# powertrain.net
KiCad netlist of a schematic drawn in Altium Designer
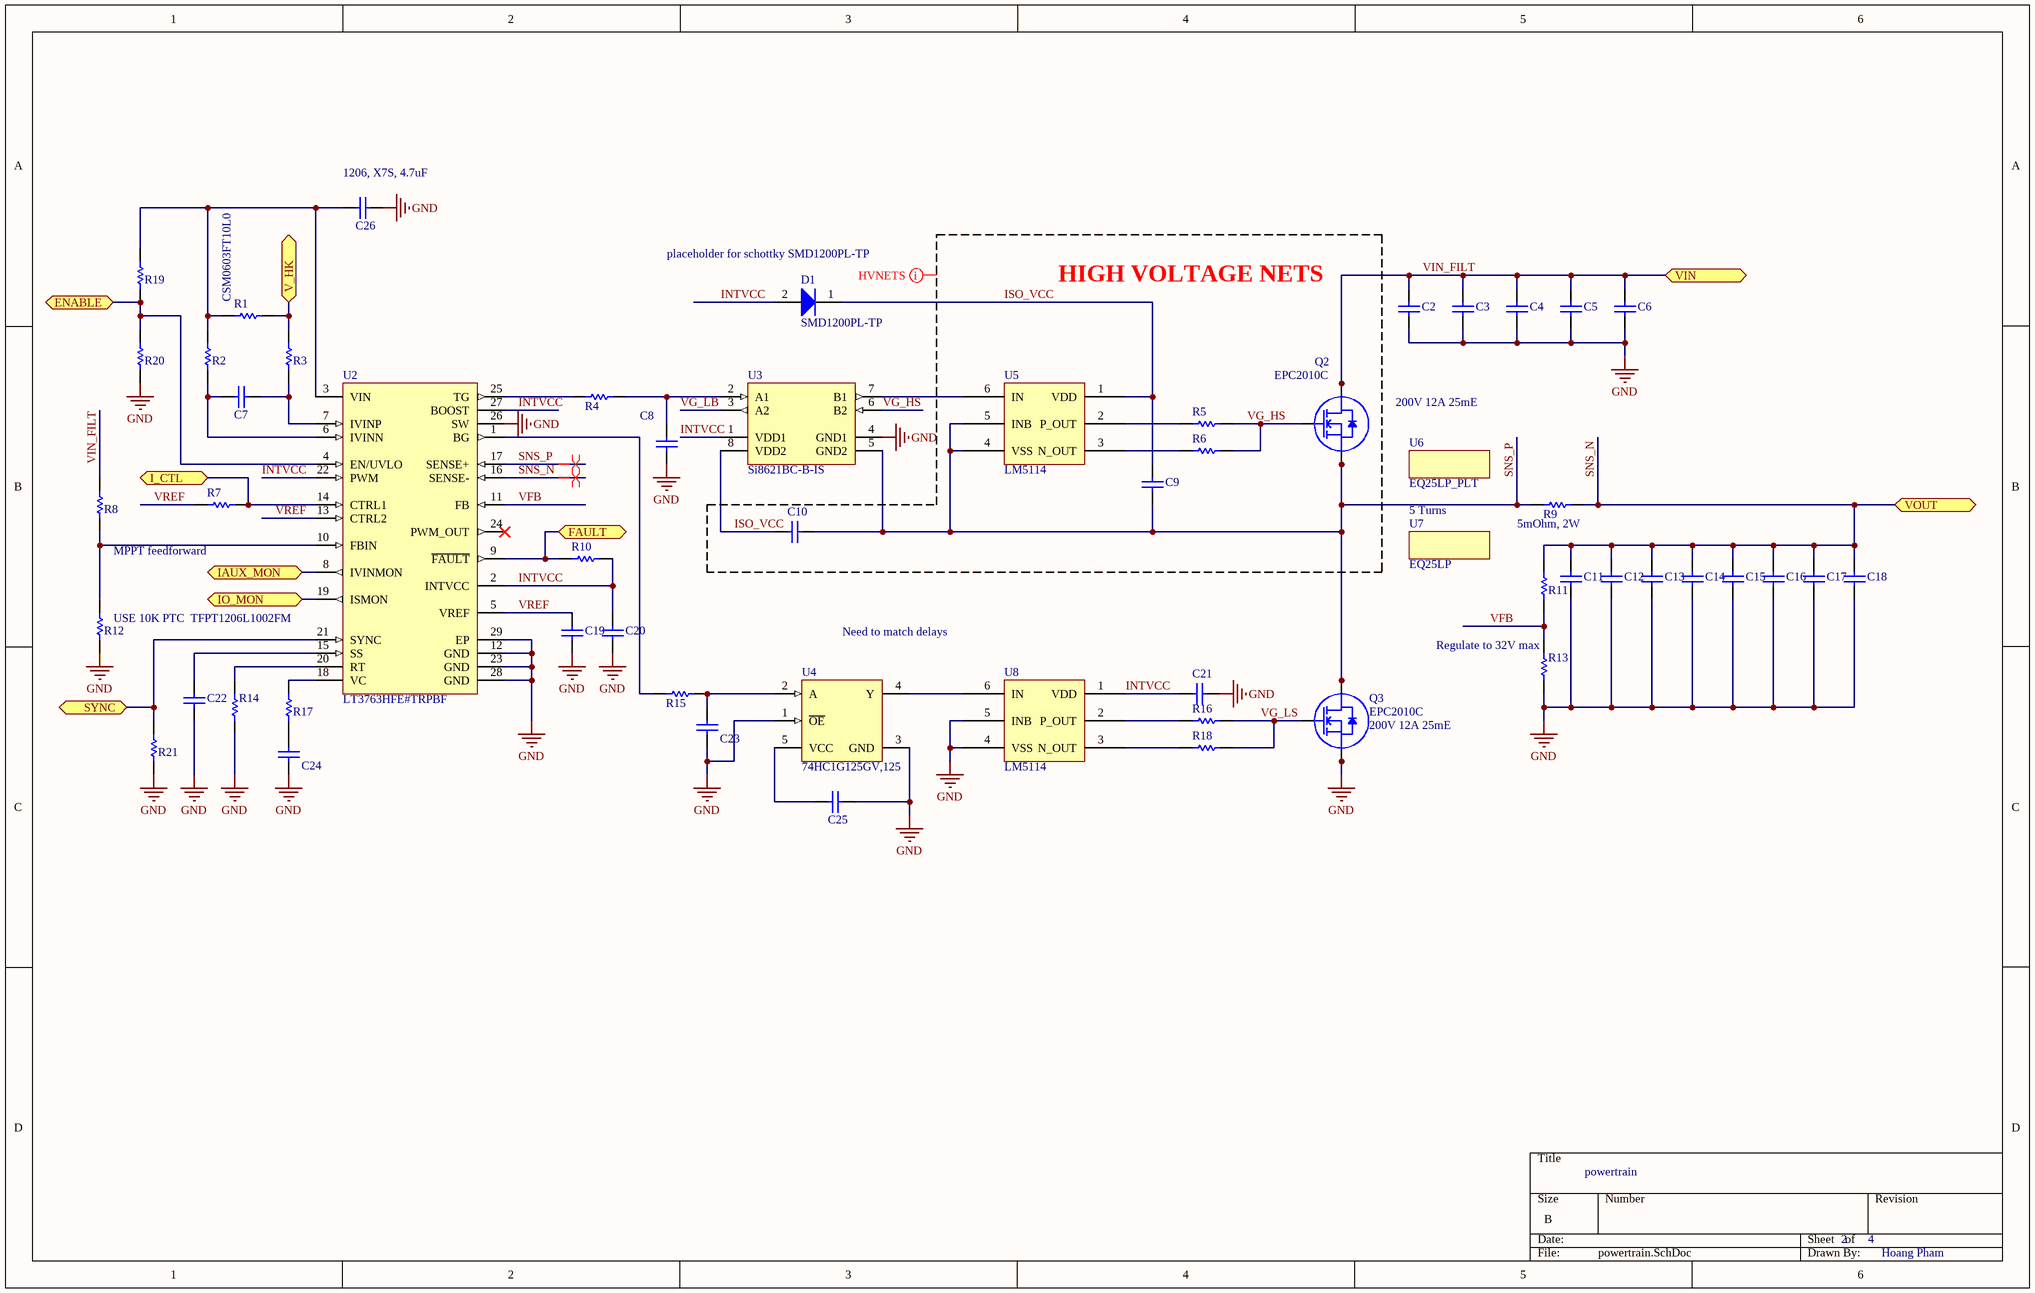
[diagram p0: powertrain.SchDoc]

(export (version "E")
  (design (tool "Eeschema 10.0.6"))
  (components
    (comp (ref "C2")
      (value "CAP 10nF 200V 0603(1608)")
      (footprint "CAPC0603(1608)100_L")
      (description "CAP 10nF 200V ±10% 0603 (1608 Metric) Thickness 1mm SMD")
      (fields (field (name "TOLERANCE") "Â±10%"))
      (libsource (lib "Altium Content Vault") (part "CAP"))
    )
    (comp (ref "C3")
      (value "CAP 10nF 200V 0603(1608)")
      (footprint "CAPC0603(1608)100_L")
      (description "CAP 10nF 200V ±10% 0603 (1608 Metric) Thickness 1mm SMD")
      (fields (field (name "TOLERANCE") "Â±10%"))
      (libsource (lib "Altium Content Vault") (part "CAP"))
    )
    (comp (ref "C4")
      (value "CAP 10nF 200V 0603(1608)")
      (footprint "CAPC0603(1608)100_L")
      (description "CAP 10nF 200V ±10% 0603 (1608 Metric) Thickness 1mm SMD")
      (fields (field (name "TOLERANCE") "Â±10%"))
      (libsource (lib "Altium Content Vault") (part "CAP"))
    )
    (comp (ref "C5")
      (value "CAP 10nF 200V 0603(1608)")
      (footprint "CAPC0603(1608)100_L")
      (description "CAP 10nF 200V ±10% 0603 (1608 Metric) Thickness 1mm SMD")
      (fields (field (name "TOLERANCE") "Â±10%"))
      (libsource (lib "Altium Content Vault") (part "CAP"))
    )
    (comp (ref "C6")
      (value "CAP 10nF 200V 0603(1608)")
      (footprint "CAPC0603(1608)100_L")
      (description "CAP 10nF 200V ±10% 0603 (1608 Metric) Thickness 1mm SMD")
      (fields (field (name "TOLERANCE") "Â±10%"))
      (libsource (lib "Altium Content Vault") (part "CAP"))
    )
    (comp (ref "C7")
      (value "CAP 1uF 10V 0402(1005)")
      (footprint "CAPC0402(1005)60_N")
      (description "CAP 1uF 10V ±10% 0402 (1005 Metric) Thickness 0.6mm SMD")
      (fields (field (name "TOLERANCE") "Â±10%"))
      (libsource (lib "Altium Content Vault") (part "CAP"))
    )
    (comp (ref "C8")
      (value "CAP 1pF 10V 0402(1005)")
      (footprint "CAPC0402(1005)60_L")
      (description "CAP 1pF 10V ±0.1pF 0402 (1005 Metric) Thickness 0.6mm SMD")
      (fields (field (name "TOLERANCE") "Â±0.1pF"))
      (libsource (lib "Altium Content Vault") (part "CAP"))
    )
    (comp (ref "C9")
      (value "CAP 220nF 10V 0402(1005)")
      (footprint "CAPC0402(1005)60_M")
      (description "CAP 220nF 10V ±10% 0402 (1005 Metric) Thickness 0.6mm SMD")
      (fields (field (name "TOLERANCE") "Â±10%"))
      (libsource (lib "Altium Content Vault") (part "CAP"))
    )
    (comp (ref "C10")
      (value "CAP 220nF 10V 0402(1005)")
      (footprint "CAPC0402(1005)60_M")
      (description "CAP 220nF 10V ±10% 0402 (1005 Metric) Thickness 0.6mm SMD")
      (fields (field (name "TOLERANCE") "Â±10%"))
      (libsource (lib "Altium Content Vault") (part "CAP"))
    )
    (comp (ref "C11")
      (value "CAP 4.7uF 100V 2220(5750)")
      (footprint "CAPC2220(5750)280_M")
      (description "CAP 4.7uF 100V ±20% 2220 (5750 Metric) Thickness 2.8mm SMD")
      (fields (field (name "TOLERANCE") "Â±20%"))
      (libsource (lib "Altium Content Vault") (part "CAP"))
    )
    (comp (ref "C12")
      (value "CAP 4.7uF 100V 2220(5750)")
      (footprint "CAPC2220(5750)280_M")
      (description "CAP 4.7uF 100V ±20% 2220 (5750 Metric) Thickness 2.8mm SMD")
      (fields (field (name "TOLERANCE") "Â±20%"))
      (libsource (lib "Altium Content Vault") (part "CAP"))
    )
    (comp (ref "C13")
      (value "CAP 4.7uF 100V 2220(5750)")
      (footprint "CAPC2220(5750)280_M")
      (description "CAP 4.7uF 100V ±20% 2220 (5750 Metric) Thickness 2.8mm SMD")
      (fields (field (name "TOLERANCE") "Â±20%"))
      (libsource (lib "Altium Content Vault") (part "CAP"))
    )
    (comp (ref "C14")
      (value "CAP 4.7uF 100V 2220(5750)")
      (footprint "CAPC2220(5750)280_M")
      (description "CAP 4.7uF 100V ±20% 2220 (5750 Metric) Thickness 2.8mm SMD")
      (fields (field (name "TOLERANCE") "Â±20%"))
      (libsource (lib "Altium Content Vault") (part "CAP"))
    )
    (comp (ref "C15")
      (value "CAP 4.7uF 100V 2220(5750)")
      (footprint "CAPC2220(5750)280_M")
      (description "CAP 4.7uF 100V ±20% 2220 (5750 Metric) Thickness 2.8mm SMD")
      (fields (field (name "TOLERANCE") "Â±20%"))
      (libsource (lib "Altium Content Vault") (part "CAP"))
    )
    (comp (ref "C16")
      (value "CAP 4.7uF 100V 2220(5750)")
      (footprint "CAPC2220(5750)280_M")
      (description "CAP 4.7uF 100V ±20% 2220 (5750 Metric) Thickness 2.8mm SMD")
      (fields (field (name "TOLERANCE") "Â±20%"))
      (libsource (lib "Altium Content Vault") (part "CAP"))
    )
    (comp (ref "C17")
      (value "CAP 4.7uF 100V 2220(5750)")
      (footprint "CAPC2220(5750)280_M")
      (description "CAP 4.7uF 100V ±20% 2220 (5750 Metric) Thickness 2.8mm SMD")
      (fields (field (name "TOLERANCE") "Â±20%"))
      (libsource (lib "Altium Content Vault") (part "CAP"))
    )
    (comp (ref "C18")
      (value "CAP 4.7uF 100V 2220(5750)")
      (footprint "CAPC2220(5750)280_M")
      (description "CAP 4.7uF 100V ±20% 2220 (5750 Metric) Thickness 2.8mm SMD")
      (fields (field (name "TOLERANCE") "Â±20%"))
      (libsource (lib "Altium Content Vault") (part "CAP"))
    )
    (comp (ref "C19")
      (value "CAP 2.2uF 10V 0402(1005)")
      (footprint "CAPC0402(1005)60_N")
      (description "CAP 2.2uF 10V ±10% 0402 (1005 Metric) Thickness 0.6mm SMD")
      (fields (field (name "TOLERANCE") "Â±10%"))
      (libsource (lib "Altium Content Vault") (part "CAP"))
    )
    (comp (ref "C20")
      (value "CAP 22uF 10V 0805(2012)")
      (footprint "CAPC0805(2012)145_L")
      (description "CAP 22uF 10V ±10% 0805 (2012 Metric) Thickness 1.45mm SMD")
      (fields (field (name "TOLERANCE") "Â±10%"))
      (libsource (lib "Altium Content Vault") (part "CAP"))
    )
    (comp (ref "C21")
      (value "CAP 220nF 10V 0402(1005)")
      (footprint "CAPC0402(1005)60_M")
      (description "CAP 220nF 10V ±10% 0402 (1005 Metric) Thickness 0.6mm SMD")
      (fields (field (name "TOLERANCE") "Â±10%"))
      (libsource (lib "Altium Content Vault") (part "CAP"))
    )
    (comp (ref "C22")
      (value "CAP 10nF 10V 0402(1005)")
      (footprint "CAPC0402(1005)60_L")
      (description "CAP 10nF 10V ±5% 0402 (1005 Metric) Thickness 0.6mm SMD")
      (fields (field (name "TOLERANCE") "Â±5%"))
      (libsource (lib "Altium Content Vault") (part "CAP"))
    )
    (comp (ref "C23")
      (value "CAP 1pF 10V 0402(1005)")
      (footprint "CAPC0402(1005)60_L")
      (description "CAP 1pF 10V ±0.1pF 0402 (1005 Metric) Thickness 0.6mm SMD")
      (fields (field (name "TOLERANCE") "Â±0.1pF"))
      (libsource (lib "Altium Content Vault") (part "CAP"))
    )
    (comp (ref "C24")
      (value "CAP 4.7nF 10V 0402(1005)")
      (footprint "CAPC0402(1005)60_M")
      (description "CAP 4.7nF 10V ±5% 0402 (1005 Metric) Thickness 0.6mm SMD")
      (fields (field (name "TOLERANCE") "Â±5%"))
      (libsource (lib "Altium Content Vault") (part "CAP"))
    )
    (comp (ref "C25")
      (value "CAP 470nF 10V 0402(1005)")
      (footprint "CAPC0402(1005)60_N")
      (description "CAP 470nF 10V ±10% 0402 (1005 Metric) Thickness 0.6mm SMD")
      (fields (field (name "TOLERANCE") "Â±10%"))
      (libsource (lib "Altium Content Vault") (part "CAP"))
    )
    (comp (ref "C26")
      (value "CAP 1uF 100V 1206(3216)")
      (footprint "CAPC1206(3216)190_M")
      (description "CAP 1uF 100V ±20% 1206 (3216 Metric) Thickness 1.9mm SMD")
      (fields (field (name "TOLERANCE") "Â±20%"))
      (libsource (lib "Altium Content Vault") (part "CAP"))
    )
    (comp (ref "D1")
      (value "SMD1200PL-TP")
      (footprint "ONSC-SOD-123-2-425-04_V")
      (description "High Voltage Switching Diode, 2-Pin SOD-123, Pb-Free, Tape and Reel")
      (fields (field (name "MANUFACTURER") "On Semiconductor") (field (name "PARTNUMBER") "MMSD103T1G"))
      (libsource (lib "Altium Content Vault") (part "ONSC-D-K1A2-2"))
    )
    (comp (ref "Q2")
      (value "EPC2010C")
      (footprint "EPC2x200L")
      (description "200V 12A 25mE")
      (fields (field (name "MFG") "EPC") (field (name "ALTIUM_VALUE") "200V 12A 25mE"))
      (libsource (lib "EPC_2017Q3") (part "EPC2010C"))
    )
    (comp (ref "Q3")
      (value "EPC2010C")
      (footprint "EPC2x200L")
      (description "200V 12A 25mE")
      (fields (field (name "MFG") "EPC") (field (name "ALTIUM_VALUE") "200V 12A 25mE"))
      (libsource (lib "EPC_2017Q3") (part "EPC2010C"))
    )
    (comp (ref "R1")
      (value "CSM0603FT10L0")
      (footprint "RESC1608X40X30ML10T10")
      (description "Chip Resistor, 10 mOhm, +/- 1%, 333 mW, -55 to 155 degC, 0603 (1608 Metric), RoHS, Tape and Reel")
      (fields (field (name "TOLERANCE") "1%"))
      (libsource (lib "Altium Content Vault") (part "RES-2"))
    )
    (comp (ref "R2")
      (value "1K 1% 0402(1005)")
      (footprint "RESC0402(1005)_L")
      (description "1K 0.063W 1% 0402 (1005 Metric)  SMD")
      (fields (field (name "TOLERANCE") "1 %") (field (name "POWER") "0.063 W"))
      (libsource (lib "Altium Content Vault") (part "RES"))
    )
    (comp (ref "R3")
      (value "1K 1% 0402(1005)")
      (footprint "RESC0402(1005)_L")
      (description "1K 0.063W 1% 0402 (1005 Metric)  SMD")
      (fields (field (name "TOLERANCE") "1 %") (field (name "POWER") "0.063 W"))
      (libsource (lib "Altium Content Vault") (part "RES"))
    )
    (comp (ref "R4")
      (value "Jumper 0402(1005)")
      (footprint "RESC0402(1005)_N")
      (description "Jumper 0402 (1005 Metric)")
      (fields (field (name "TOLERANCE") "None"))
      (libsource (lib "Altium Content Vault") (part "RES"))
    )
    (comp (ref "R5")
      (value "Jumper 0402(1005)")
      (footprint "RESC0402(1005)_N")
      (description "Jumper 0402 (1005 Metric)")
      (fields (field (name "TOLERANCE") "None"))
      (libsource (lib "Altium Content Vault") (part "RES"))
    )
    (comp (ref "R6")
      (value "Jumper 0402(1005)")
      (footprint "RESC0402(1005)_N")
      (description "Jumper 0402 (1005 Metric)")
      (fields (field (name "TOLERANCE") "None"))
      (libsource (lib "Altium Content Vault") (part "RES"))
    )
    (comp (ref "R7")
      (value "10K 1% 0402(1005)")
      (footprint "RESC0402(1005)_N")
      (description "10K 0.063W 1% 0402 (1005 Metric)  SMD")
      (fields (field (name "TOLERANCE") "1 %") (field (name "POWER") "0.063 W"))
      (libsource (lib "Altium Content Vault") (part "RES"))
    )
    (comp (ref "R8")
      (value "475K 1% 0603(1608)")
      (footprint "RESC0603(1608)_M")
      (description "475K 0.1W 1% 0603 (1608 Metric)  SMD")
      (fields (field (name "POWER") "0.1 W") (field (name "TOLERANCE") "1 %"))
      (libsource (lib "Altium Content Vault") (part "RES"))
    )
    (comp (ref "R9")
      (value "Jumper 2010(5025)")
      (footprint "RESC2010(5025)_M")
      (description "Jumper 2010 (5025 Metric)")
      (fields (field (name "TOLERANCE") "None"))
      (libsource (lib "Altium Content Vault") (part "RES"))
    )
    (comp (ref "R10")
      (value "47K5 1% 0402(1005)")
      (footprint "RESC0402(1005)_M")
      (description "47K5 0.063W 1% 0402 (1005 Metric)  SMD")
      (fields (field (name "POWER") "0.063 W") (field (name "TOLERANCE") "1 %"))
      (libsource (lib "Altium Content Vault") (part "RES"))
    )
    (comp (ref "R11")
      (value "255K 1% 0603(1608)")
      (footprint "RESC0603(1608)_N")
      (description "255K 0.1W 1% 0603 (1608 Metric)  SMD")
      (fields (field (name "TOLERANCE") "1 %") (field (name "POWER") "0.1 W"))
      (libsource (lib "Altium Content Vault") (part "RES"))
    )
    (comp (ref "R12")
      (value "10K 5% 1206(3216)")
      (footprint "RESC1206(3216)_M")
      (description "10K 0.25W 5% 1206 (3216 Metric)  SMD")
      (fields (field (name "POWER") "0.25 W") (field (name "TOLERANCE") "5 %"))
      (libsource (lib "Altium Content Vault") (part "RES"))
    )
    (comp (ref "R13")
      (value "10K 1% 0402(1005)")
      (footprint "RESC0402(1005)_N")
      (description "10K 0.063W 1% 0402 (1005 Metric)  SMD")
      (fields (field (name "TOLERANCE") "1 %") (field (name "POWER") "0.063 W"))
      (libsource (lib "Altium Content Vault") (part "CMP-1011-00623-1"))
    )
    (comp (ref "R14")
      (value "90K9 1% 0402(1005)")
      (footprint "RESC0402(1005)_N")
      (description "90K9 0.063W 1% 0402 (1005 Metric)  SMD")
      (fields (field (name "TOLERANCE") "1 %") (field (name "POWER") "0.063 W"))
      (libsource (lib "Altium Content Vault") (part "RES"))
    )
    (comp (ref "R15")
      (value "Jumper 0402(1005)")
      (footprint "RESC0402(1005)_N")
      (description "Jumper 0402 (1005 Metric)")
      (fields (field (name "TOLERANCE") "None"))
      (libsource (lib "Altium Content Vault") (part "RES"))
    )
    (comp (ref "R16")
      (value "Jumper 0402(1005)")
      (footprint "RESC0402(1005)_N")
      (description "Jumper 0402 (1005 Metric)")
      (fields (field (name "TOLERANCE") "None"))
      (libsource (lib "Altium Content Vault") (part "RES"))
    )
    (comp (ref "R17")
      (value "59K 1% 0402(1005)")
      (footprint "RESC0402(1005)_L")
      (description "59K 0.063W 1% 0402 (1005 Metric)  SMD")
      (fields (field (name "POWER") "0.063 W") (field (name "TOLERANCE") "1 %"))
      (libsource (lib "Altium Content Vault") (part "RES"))
    )
    (comp (ref "R18")
      (value "Jumper 0402(1005)")
      (footprint "RESC0402(1005)_N")
      (description "Jumper 0402 (1005 Metric)")
      (fields (field (name "TOLERANCE") "None"))
      (libsource (lib "Altium Content Vault") (part "RES"))
    )
    (comp (ref "R19")
      (value "69R8 1% 0402(1005)")
      (footprint "RESC0402(1005)_M")
      (description "69R8 0.063W 1% 0402 (1005 Metric)  SMD")
      (fields (field (name "TOLERANCE") "1 %") (field (name "POWER") "0.063 W"))
      (libsource (lib "Altium Content Vault") (part "RES"))
    )
    (comp (ref "R20")
      (value "3K3 5% 0402(1005)")
      (footprint "RESC0402(1005)_L")
      (description "3K3 0.063W 5% 0402 (1005 Metric)  SMD")
      (fields (field (name "POWER") "0.063 W") (field (name "TOLERANCE") "5 %"))
      (libsource (lib "Altium Content Vault") (part "RES"))
    )
    (comp (ref "R21")
      (value "10K 5% 0402(1005)")
      (footprint "RESC0402(1005)_N")
      (description "10K 0.063W 5% 0402 (1005 Metric)  SMD")
      (fields (field (name "TOLERANCE") "5 %") (field (name "POWER") "0.063 W"))
      (libsource (lib "Altium Content Vault") (part "RES"))
    )
    (comp (ref "U2")
      (value "LT3763HFE#TRPBF")
      (footprint "LT-FE-28-EPV-EB_N")
      (fields (field (name "MANUFACTURER") "Linear Technology"))
      (libsource (lib "Altium Content Vault") (part "LT-LT3763-FE-28"))
    )
    (comp (ref "U3")
      (value "Si8621BC-B-IS")
      (footprint "SLAB-SOIC-8-NB_M")
      (fields (field (name "MANUFACTURER") "Silicon Labs"))
      (libsource (lib "Altium Content Vault") (part "SLAB-Si8X21XX-SOIC-8-8"))
    )
    (comp (ref "U4")
      (value "74HC1G125GV,125")
      (footprint "NXP-SOT753_V")
      (description "High-Speed, Si-Gate CMOS Device, 2 to 6 V, -40 to 125 degC, 5-Pin SC-74A (SOT753), RoHS, Reel")
      (fields (field (name "MANUFACTURER") "NXP Semiconductors"))
      (libsource (lib "Altium Content Vault") (part "NXP-74HC1G125-5"))
    )
    (comp (ref "U5") (value "LM5114") (libsource (lib "LM5114") (part "LM5114")))
    (comp (ref "U6") (value "EQ25LP_PLT") (libsource (lib "EQ25LP_PLT") (part "EQ25LP_PLT")))
    (comp (ref "U7") (value "EQ25LP") (libsource (lib "EQ25LP") (part "EQ25LP")))
    (comp (ref "U8") (value "LM5114") (libsource (lib "LM5114") (part "LM5114")))
  )
  (nets
    (net (code "1") (name "/ENABLE") (class "Default")
      (node (ref "R19") (pin "1") (pinfunction "1_1") (pintype "passive"))
      (node (ref "R20") (pin "2") (pinfunction "2_2") (pintype "passive"))
      (node (ref "U2") (pin "4") (pinfunction "EN/UVLO_4") (pintype "input"))
    )
    (net (code "2") (name "/FAULT") (class "Default")
      (node (ref "R10") (pin "1") (pinfunction "1_1") (pintype "passive"))
      (node (ref "U2") (pin "9") (pinfunction "~{FAULT}_9") (pintype "output"))
    )
    (net (code "3") (name "/IAUX_MON") (class "Default")
      (node (ref "U2") (pin "8") (pinfunction "IVINMON_8") (pintype "output"))
    )
    (net (code "4") (name "/INTVCC") (class "Default")
      (node (ref "C20") (pin "2") (pinfunction "2_2") (pintype "passive"))
      (node (ref "C21") (pin "2") (pinfunction "2_2") (pintype "passive"))
      (node (ref "D1") (pin "2") (pinfunction "A_2") (pintype "passive"))
      (node (ref "R10") (pin "2") (pinfunction "2_2") (pintype "passive"))
      (node (ref "U2") (pin "2") (pinfunction "INTVCC_2") (pintype "power_in"))
      (node (ref "U2") (pin "22") (pinfunction "PWM_22") (pintype "input"))
      (node (ref "U2") (pin "27") (pinfunction "BOOST_27") (pintype "passive"))
      (node (ref "U3") (pin "1") (pinfunction "VDD1_1") (pintype "power_in"))
      (node (ref "U8") (pin "1") (pinfunction "VDD_1") (pintype "power_in"))
    )
    (net (code "5") (name "/IO_MON") (class "Default")
      (node (ref "U2") (pin "19") (pinfunction "ISMON_19") (pintype "output"))
    )
    (net (code "6") (name "/ISO_VCC") (class "Default")
      (node (ref "C10") (pin "2") (pinfunction "2_2") (pintype "passive"))
      (node (ref "C9") (pin "2") (pinfunction "2_2") (pintype "passive"))
      (node (ref "D1") (pin "1") (pinfunction "K_1") (pintype "passive"))
      (node (ref "U3") (pin "8") (pinfunction "VDD2_8") (pintype "power_in"))
      (node (ref "U5") (pin "1") (pinfunction "VDD_1") (pintype "power_in"))
    )
    (net (code "7") (name "/I_CTL") (class "Default")
      (node (ref "R7") (pin "1") (pinfunction "1_1") (pintype "passive"))
      (node (ref "U2") (pin "14") (pinfunction "CTRL1_14") (pintype "input"))
    )
    (net (code "8") (name "/SNS_N") (class "Default")
      (node (ref "C11") (pin "2") (pinfunction "2_2") (pintype "passive"))
      (node (ref "C12") (pin "2") (pinfunction "2_2") (pintype "passive"))
      (node (ref "C13") (pin "2") (pinfunction "2_2") (pintype "passive"))
      (node (ref "C14") (pin "2") (pinfunction "2_2") (pintype "passive"))
      (node (ref "C15") (pin "2") (pinfunction "2_2") (pintype "passive"))
      (node (ref "C16") (pin "2") (pinfunction "2_2") (pintype "passive"))
      (node (ref "C17") (pin "2") (pinfunction "2_2") (pintype "passive"))
      (node (ref "C18") (pin "2") (pinfunction "2_2") (pintype "passive"))
      (node (ref "R11") (pin "2") (pinfunction "2_2") (pintype "passive"))
      (node (ref "R9") (pin "2") (pinfunction "2_2") (pintype "passive"))
      (node (ref "U2") (pin "16") (pinfunction "SENSE-_16") (pintype "input"))
    )
    (net (code "9") (name "/SNS_P") (class "Default")
      (node (ref "C10") (pin "1") (pinfunction "1_1") (pintype "passive"))
      (node (ref "C9") (pin "1") (pinfunction "1_1") (pintype "passive"))
      (node (ref "Q2") (pin "2") (pinfunction "SS_2") (pintype "open_emitter"))
      (node (ref "Q2") (pin "4") (pinfunction "SP1_4") (pintype "open_emitter"))
      (node (ref "Q2") (pin "6") (pinfunction "SP2_6") (pintype "open_emitter"))
      (node (ref "Q3") (pin "3") (pinfunction "D1_3") (pintype "open_collector"))
      (node (ref "Q3") (pin "5") (pinfunction "D2_5") (pintype "open_collector"))
      (node (ref "Q3") (pin "7") (pinfunction "D3_7") (pintype "open_collector"))
      (node (ref "R9") (pin "1") (pinfunction "1_1") (pintype "passive"))
      (node (ref "U2") (pin "17") (pinfunction "SENSE+_17") (pintype "input"))
      (node (ref "U3") (pin "5") (pinfunction "GND2_5") (pintype "power_in"))
      (node (ref "U5") (pin "4") (pinfunction "VSS_4") (pintype "power_in"))
      (node (ref "U5") (pin "5") (pinfunction "INB_5") (pintype "passive"))
    )
    (net (code "10") (name "/SYNC") (class "Default")
      (node (ref "R21") (pin "2") (pinfunction "2_2") (pintype "passive"))
      (node (ref "U2") (pin "21") (pinfunction "SYNC_21") (pintype "input"))
    )
    (net (code "11") (name "/VFB") (class "Default")
      (node (ref "R11") (pin "1") (pinfunction "1_1") (pintype "passive"))
      (node (ref "R13") (pin "2") (pinfunction "2_2") (pintype "passive"))
      (node (ref "U2") (pin "11") (pinfunction "FB_11") (pintype "input"))
    )
    (net (code "12") (name "/VG_HS") (class "Default")
      (node (ref "Q2") (pin "1") (pinfunction "G_1") (pintype "passive"))
      (node (ref "R5") (pin "2") (pinfunction "2_2") (pintype "passive"))
      (node (ref "R6") (pin "2") (pinfunction "2_2") (pintype "passive"))
      (node (ref "U3") (pin "6") (pinfunction "B2_6") (pintype "input"))
    )
    (net (code "13") (name "/VG_LB") (class "Default")
      (node (ref "U3") (pin "3") (pinfunction "A2_3") (pintype "output"))
    )
    (net (code "14") (name "/VG_LS") (class "Default")
      (node (ref "Q3") (pin "1") (pinfunction "G_1") (pintype "passive"))
      (node (ref "R16") (pin "2") (pinfunction "2_2") (pintype "passive"))
      (node (ref "R18") (pin "2") (pinfunction "2_2") (pintype "passive"))
    )
    (net (code "15") (name "/VIN_FILT") (class "Default")
      (node (ref "C2") (pin "2") (pinfunction "2_2") (pintype "passive"))
      (node (ref "C3") (pin "2") (pinfunction "2_2") (pintype "passive"))
      (node (ref "C4") (pin "2") (pinfunction "2_2") (pintype "passive"))
      (node (ref "C5") (pin "2") (pinfunction "2_2") (pintype "passive"))
      (node (ref "C6") (pin "2") (pinfunction "2_2") (pintype "passive"))
      (node (ref "Q2") (pin "3") (pinfunction "D1_3") (pintype "open_collector"))
      (node (ref "Q2") (pin "5") (pinfunction "D2_5") (pintype "open_collector"))
      (node (ref "Q2") (pin "7") (pinfunction "D3_7") (pintype "open_collector"))
      (node (ref "R8") (pin "2") (pinfunction "2_2") (pintype "passive"))
    )
    (net (code "16") (name "/VREF") (class "Default")
      (node (ref "C19") (pin "2") (pinfunction "2_2") (pintype "passive"))
      (node (ref "R7") (pin "2") (pinfunction "2_2") (pintype "passive"))
      (node (ref "U2") (pin "13") (pinfunction "CTRL2_13") (pintype "input"))
      (node (ref "U2") (pin "5") (pinfunction "VREF_5") (pintype "power_in"))
    )
    (net (code "17") (name "/V_HK") (class "Default")
      (node (ref "R1") (pin "2") (pinfunction "2_2") (pintype "passive"))
      (node (ref "R3") (pin "2") (pinfunction "2_2") (pintype "passive"))
    )
    (net (code "18") (name "GND") (class "Default")
      (node (ref "C11") (pin "1") (pinfunction "1_1") (pintype "passive"))
      (node (ref "C12") (pin "1") (pinfunction "1_1") (pintype "passive"))
      (node (ref "C13") (pin "1") (pinfunction "1_1") (pintype "passive"))
      (node (ref "C14") (pin "1") (pinfunction "1_1") (pintype "passive"))
      (node (ref "C15") (pin "1") (pinfunction "1_1") (pintype "passive"))
      (node (ref "C16") (pin "1") (pinfunction "1_1") (pintype "passive"))
      (node (ref "C17") (pin "1") (pinfunction "1_1") (pintype "passive"))
      (node (ref "C18") (pin "1") (pinfunction "1_1") (pintype "passive"))
      (node (ref "C19") (pin "1") (pinfunction "1_1") (pintype "passive"))
      (node (ref "C2") (pin "1") (pinfunction "1_1") (pintype "passive"))
      (node (ref "C20") (pin "1") (pinfunction "1_1") (pintype "passive"))
      (node (ref "C21") (pin "1") (pinfunction "1_1") (pintype "passive"))
      (node (ref "C22") (pin "1") (pinfunction "1_1") (pintype "passive"))
      (node (ref "C23") (pin "1") (pinfunction "1_1") (pintype "passive"))
      (node (ref "C24") (pin "1") (pinfunction "1_1") (pintype "passive"))
      (node (ref "C25") (pin "2") (pinfunction "2_2") (pintype "passive"))
      (node (ref "C26") (pin "2") (pinfunction "2_2") (pintype "passive"))
      (node (ref "C3") (pin "1") (pinfunction "1_1") (pintype "passive"))
      (node (ref "C4") (pin "1") (pinfunction "1_1") (pintype "passive"))
      (node (ref "C5") (pin "1") (pinfunction "1_1") (pintype "passive"))
      (node (ref "C6") (pin "1") (pinfunction "1_1") (pintype "passive"))
      (node (ref "C8") (pin "1") (pinfunction "1_1") (pintype "passive"))
      (node (ref "Q3") (pin "2") (pinfunction "SS_2") (pintype "open_emitter"))
      (node (ref "Q3") (pin "4") (pinfunction "SP1_4") (pintype "open_emitter"))
      (node (ref "Q3") (pin "6") (pinfunction "SP2_6") (pintype "open_emitter"))
      (node (ref "R12") (pin "1") (pinfunction "1_1") (pintype "passive"))
      (node (ref "R13") (pin "1") (pinfunction "1_1") (pintype "passive"))
      (node (ref "R14") (pin "1") (pinfunction "1_1") (pintype "passive"))
      (node (ref "R20") (pin "1") (pinfunction "1_1") (pintype "passive"))
      (node (ref "R21") (pin "1") (pinfunction "1_1") (pintype "passive"))
      (node (ref "U2") (pin "12") (pinfunction "GND_12") (pintype "power_in"))
      (node (ref "U2") (pin "23") (pinfunction "GND_23") (pintype "power_in"))
      (node (ref "U2") (pin "26") (pinfunction "SW_26") (pintype "passive"))
      (node (ref "U2") (pin "28") (pinfunction "GND_28") (pintype "power_in"))
      (node (ref "U2") (pin "29") (pinfunction "EP_29") (pintype "power_in"))
      (node (ref "U3") (pin "4") (pinfunction "GND1_4") (pintype "power_in"))
      (node (ref "U4") (pin "1") (pinfunction "~{OE}_1") (pintype "input"))
      (node (ref "U4") (pin "3") (pinfunction "GND_3") (pintype "power_in"))
      (node (ref "U8") (pin "4") (pinfunction "VSS_4") (pintype "power_in"))
      (node (ref "U8") (pin "5") (pinfunction "INB_5") (pintype "passive"))
    )
    (net (code "19") (name "Net-(C24-Pad2)") (class "Default")
      (node (ref "C24") (pin "2") (pinfunction "2_2") (pintype "passive"))
      (node (ref "R17") (pin "1") (pinfunction "1_1") (pintype "passive"))
    )
    (net (code "20") (name "Net-(U2-BG)") (class "Default")
      (node (ref "R15") (pin "1") (pinfunction "1_1") (pintype "passive"))
      (node (ref "U2") (pin "1") (pinfunction "BG_1") (pintype "output"))
    )
    (net (code "21") (name "Net-(U2-FBIN)") (class "Default")
      (node (ref "R12") (pin "2") (pinfunction "2_2") (pintype "passive"))
      (node (ref "R8") (pin "1") (pinfunction "1_1") (pintype "passive"))
      (node (ref "U2") (pin "10") (pinfunction "FBIN_10") (pintype "input"))
    )
    (net (code "22") (name "Net-(U2-IVINN)") (class "Default")
      (node (ref "C7") (pin "1") (pinfunction "1_1") (pintype "passive"))
      (node (ref "R2") (pin "1") (pinfunction "1_1") (pintype "passive"))
      (node (ref "U2") (pin "6") (pinfunction "IVINN_6") (pintype "input"))
    )
    (net (code "23") (name "Net-(U2-IVINP)") (class "Default")
      (node (ref "C7") (pin "2") (pinfunction "2_2") (pintype "passive"))
      (node (ref "R3") (pin "1") (pinfunction "1_1") (pintype "passive"))
      (node (ref "U2") (pin "7") (pinfunction "IVINP_7") (pintype "input"))
    )
    (net (code "24") (name "Net-(U2-RT)") (class "Default")
      (node (ref "R14") (pin "2") (pinfunction "2_2") (pintype "passive"))
      (node (ref "U2") (pin "20") (pinfunction "RT_20") (pintype "passive"))
    )
    (net (code "25") (name "Net-(U2-SS)") (class "Default")
      (node (ref "C22") (pin "2") (pinfunction "2_2") (pintype "passive"))
      (node (ref "U2") (pin "15") (pinfunction "SS_15") (pintype "input"))
    )
    (net (code "26") (name "Net-(U2-TG)") (class "Default")
      (node (ref "R4") (pin "1") (pinfunction "1_1") (pintype "passive"))
      (node (ref "U2") (pin "25") (pinfunction "TG_25") (pintype "output"))
    )
    (net (code "27") (name "Net-(U2-VC)") (class "Default")
      (node (ref "R17") (pin "2") (pinfunction "2_2") (pintype "passive"))
      (node (ref "U2") (pin "18") (pinfunction "VC_18") (pintype "passive"))
    )
    (net (code "28") (name "Net-(U2-VIN)") (class "Default")
      (node (ref "C26") (pin "1") (pinfunction "1_1") (pintype "passive"))
      (node (ref "R1") (pin "1") (pinfunction "1_1") (pintype "passive"))
      (node (ref "R19") (pin "2") (pinfunction "2_2") (pintype "passive"))
      (node (ref "R2") (pin "2") (pinfunction "2_2") (pintype "passive"))
      (node (ref "U2") (pin "3") (pinfunction "VIN_3") (pintype "power_in"))
    )
    (net (code "29") (name "Net-(U3-A1)") (class "Default")
      (node (ref "C8") (pin "2") (pinfunction "2_2") (pintype "passive"))
      (node (ref "R4") (pin "2") (pinfunction "2_2") (pintype "passive"))
      (node (ref "U3") (pin "2") (pinfunction "A1_2") (pintype "input"))
    )
    (net (code "30") (name "Net-(U3-B1)") (class "Default")
      (node (ref "U3") (pin "7") (pinfunction "B1_7") (pintype "output"))
      (node (ref "U5") (pin "6") (pinfunction "IN_6") (pintype "passive"))
    )
    (net (code "31") (name "Net-(U4-A)") (class "Default")
      (node (ref "C23") (pin "2") (pinfunction "2_2") (pintype "passive"))
      (node (ref "R15") (pin "2") (pinfunction "2_2") (pintype "passive"))
      (node (ref "U4") (pin "2") (pinfunction "A_2") (pintype "input"))
    )
    (net (code "32") (name "Net-(U4-VCC)") (class "Default")
      (node (ref "C25") (pin "1") (pinfunction "1_1") (pintype "passive"))
      (node (ref "U4") (pin "5") (pinfunction "VCC_5") (pintype "power_in"))
    )
    (net (code "33") (name "Net-(U4-Y)") (class "Default")
      (node (ref "U4") (pin "4") (pinfunction "Y_4") (pintype "tri_state"))
      (node (ref "U8") (pin "6") (pinfunction "IN_6") (pintype "passive"))
    )
    (net (code "34") (name "Net-(U5-N_OUT)") (class "Default")
      (node (ref "R6") (pin "1") (pinfunction "1_1") (pintype "passive"))
      (node (ref "U5") (pin "3") (pinfunction "N_OUT_3") (pintype "passive"))
    )
    (net (code "35") (name "Net-(U5-P_OUT)") (class "Default")
      (node (ref "R5") (pin "1") (pinfunction "1_1") (pintype "passive"))
      (node (ref "U5") (pin "2") (pinfunction "P_OUT_2") (pintype "passive"))
    )
    (net (code "36") (name "Net-(U8-N_OUT)") (class "Default")
      (node (ref "R18") (pin "1") (pinfunction "1_1") (pintype "passive"))
      (node (ref "U8") (pin "3") (pinfunction "N_OUT_3") (pintype "passive"))
    )
    (net (code "37") (name "Net-(U8-P_OUT)") (class "Default")
      (node (ref "R16") (pin "1") (pinfunction "1_1") (pintype "passive"))
      (node (ref "U8") (pin "2") (pinfunction "P_OUT_2") (pintype "passive"))
    )
    (net (code "38") (name "unconnected-(U2-PWM_OUT-Pad24)") (class "Default")
      (node (ref "U2") (pin "24") (pinfunction "PWM_OUT_24") (pintype "output+no_connect"))
    )
  )
)
